# PR5002-S.net
KiCad netlist of a schematic drawn in EAGLE
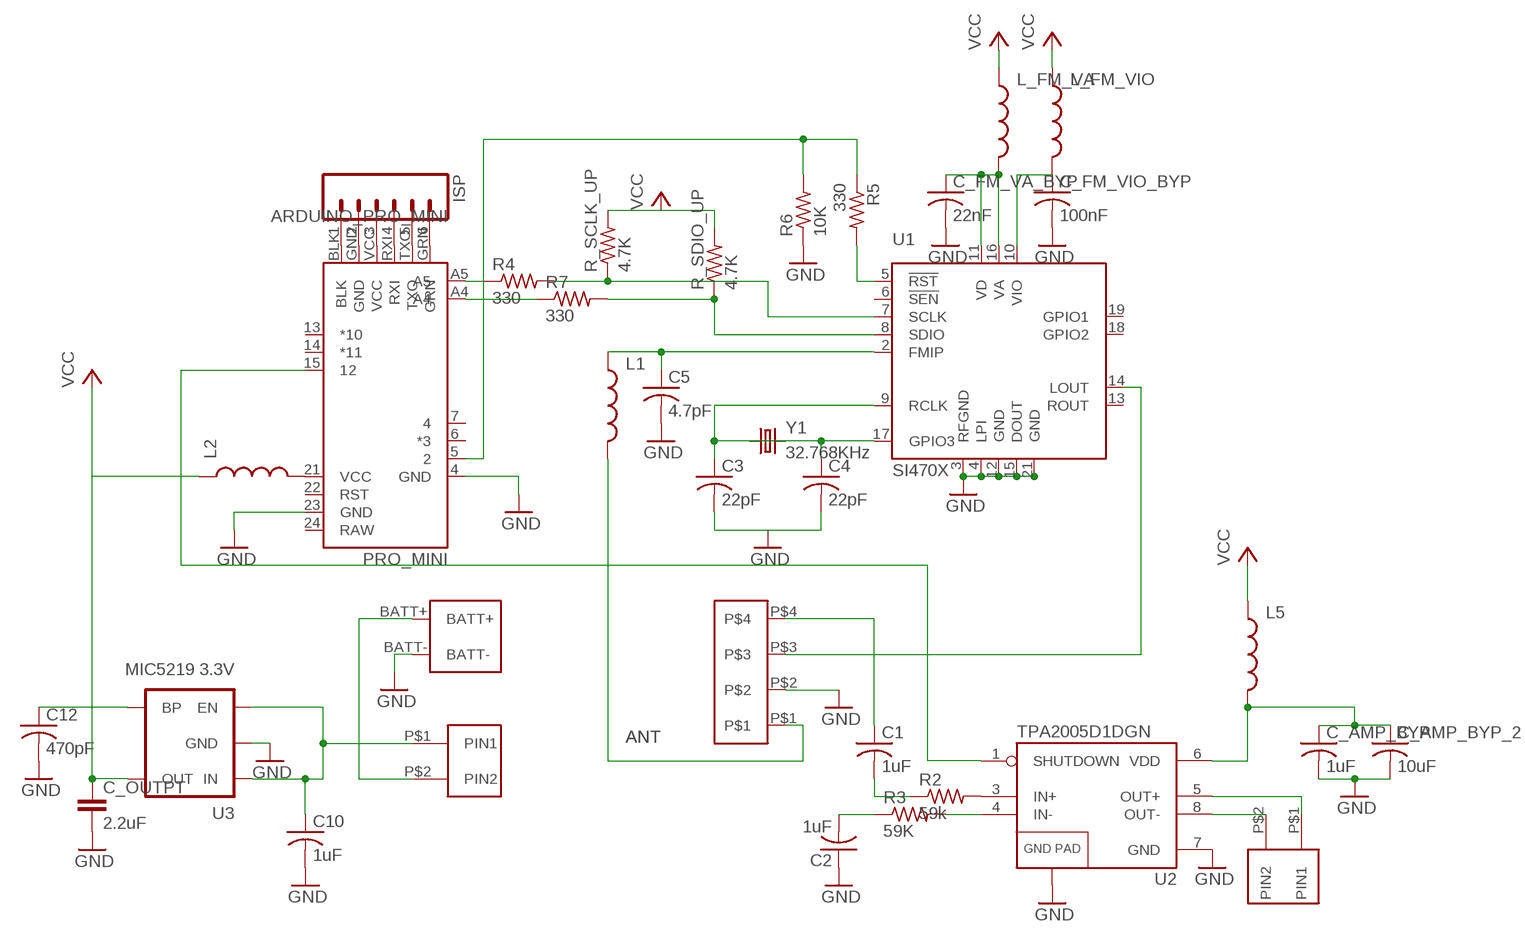
[diagram p0: schematic, sheet 1]

(export (version "E")
  (design (tool "Eeschema 10.0.6"))
  (components
    (comp (ref "ANT/POT_VOL")
      (value "OSTVN04")
      (footprint "eagle-import:OSTVN04")
      (libsource (lib "eagle-import") (part "OSTVN04"))
    )
    (comp (ref "BATT_IN")
      (value "KEYSTONE_2479_3XAAA_BOTTOM")
      (footprint "eagle-import:KEYSTONE_2479_3XAAA_BOTTOM")
      (libsource (lib "eagle-import") (part "KEYSTONE_2479_3XAAA_BOTTOM"))
    )
    (comp (ref "C1")
      (value "1uF")
      (footprint "eagle-import:C0603")
      (libsource (lib "eagle-import") (part "C-USC0603"))
    )
    (comp (ref "C2")
      (value "1uF")
      (footprint "eagle-import:C0603")
      (libsource (lib "eagle-import") (part "C-USC0603"))
    )
    (comp (ref "C3")
      (value "22pF")
      (footprint "eagle-import:C0603")
      (libsource (lib "eagle-import") (part "C-USC0603"))
    )
    (comp (ref "C4")
      (value "22pF")
      (footprint "eagle-import:C0603")
      (libsource (lib "eagle-import") (part "C-USC0603"))
    )
    (comp (ref "C5")
      (value "4.7pF")
      (footprint "eagle-import:C0603")
      (libsource (lib "eagle-import") (part "C-USC0603"))
    )
    (comp (ref "C10")
      (value "1uF")
      (footprint "eagle-import:C0603")
      (libsource (lib "eagle-import") (part "C-USC0603"))
    )
    (comp (ref "C12")
      (value "470pF")
      (footprint "eagle-import:C0603")
      (libsource (lib "eagle-import") (part "C-USC0603"))
    )
    (comp (ref "C_AMP_BYP")
      (value "1uF")
      (footprint "eagle-import:C0603")
      (libsource (lib "eagle-import") (part "C-USC0603"))
    )
    (comp (ref "C_AMP_BYP_2")
      (value "10uF")
      (footprint "eagle-import:C0603")
      (libsource (lib "eagle-import") (part "C-USC0603"))
    )
    (comp (ref "C_FM_VA_BYP")
      (value "22nF")
      (footprint "eagle-import:C0603")
      (libsource (lib "eagle-import") (part "C-USC0603"))
    )
    (comp (ref "C_FM_VIO_BYP")
      (value "100nF")
      (footprint "eagle-import:C0603")
      (libsource (lib "eagle-import") (part "C-USC0603"))
    )
    (comp (ref "C_OUTPT")
      (value "2.2uF")
      (footprint "eagle-import:VISHAY_TR3C")
      (libsource (lib "eagle-import") (part "VISHAY_TR3C"))
    )
    (comp (ref "ISP")
      (value "M06LOCK_LONGPADS")
      (footprint "eagle-import:1X06_LOCK_LONGPADS")
      (libsource (lib "eagle-import") (part "M06LOCK_LONGPADS"))
    )
    (comp (ref "L1")
      (value "INDUCTOR0805")
      (footprint "eagle-import:0805")
      (libsource (lib "eagle-import") (part "INDUCTOR0805"))
    )
    (comp (ref "L2")
      (value "INDUCTOR0603")
      (footprint "eagle-import:0603")
      (libsource (lib "eagle-import") (part "INDUCTOR0603"))
    )
    (comp (ref "L5")
      (value "INDUCTOR0603")
      (footprint "eagle-import:0603")
      (libsource (lib "eagle-import") (part "INDUCTOR0603"))
    )
    (comp (ref "L_FM_VA")
      (value "INDUCTOR0603")
      (footprint "eagle-import:0603")
      (libsource (lib "eagle-import") (part "INDUCTOR0603"))
    )
    (comp (ref "L_FM_VIO")
      (value "INDUCTOR0603")
      (footprint "eagle-import:0603")
      (libsource (lib "eagle-import") (part "INDUCTOR0603"))
    )
    (comp (ref "POT_SW")
      (value "OSTVN02")
      (footprint "eagle-import:OSTVN02")
      (libsource (lib "eagle-import") (part "OSTVN02"))
    )
    (comp (ref "PRO_MINI")
      (value "ARDUINO_PRO_MINI")
      (footprint "eagle-import:ARDUINO_PRO_MINI")
      (libsource (lib "eagle-import") (part "ARDUINO_PRO_MINI"))
    )
    (comp (ref "R2")
      (value "59k")
      (footprint "eagle-import:R0603")
      (libsource (lib "eagle-import") (part "R-US_R0603"))
    )
    (comp (ref "R3")
      (value "59K")
      (footprint "eagle-import:R0603")
      (libsource (lib "eagle-import") (part "R-US_R0603"))
    )
    (comp (ref "R4")
      (value "330")
      (footprint "eagle-import:R0603")
      (libsource (lib "eagle-import") (part "R-US_R0603"))
    )
    (comp (ref "R5")
      (value "330")
      (footprint "eagle-import:R0603")
      (libsource (lib "eagle-import") (part "R-US_R0603"))
    )
    (comp (ref "R6")
      (value "10K")
      (footprint "eagle-import:R0603")
      (libsource (lib "eagle-import") (part "R-US_R0603"))
    )
    (comp (ref "R7")
      (value "330")
      (footprint "eagle-import:R0603")
      (libsource (lib "eagle-import") (part "R-US_R0603"))
    )
    (comp (ref "R_SCLK_UP")
      (value "4.7K")
      (footprint "eagle-import:R0603")
      (libsource (lib "eagle-import") (part "R-US_R0603"))
    )
    (comp (ref "R_SDIO_UP")
      (value "4.7K")
      (footprint "eagle-import:R0603")
      (libsource (lib "eagle-import") (part "R-US_R0603"))
    )
    (comp (ref "SPKR")
      (value "OSTVN02")
      (footprint "eagle-import:OSTVN02")
      (libsource (lib "eagle-import") (part "OSTVN02"))
    )
    (comp (ref "U1")
      (value "SI470X")
      (footprint "eagle-import:SI470X")
      (libsource (lib "eagle-import") (part "SI470X"))
    )
    (comp (ref "U2")
      (value "TPA2005D1DGN")
      (footprint "eagle-import:POWER-SOP8")
      (libsource (lib "eagle-import") (part "TPA2005D1DGN"))
    )
    (comp (ref "U3")
      (value "MIC5219 3.3V")
      (footprint "eagle-import:SOT23-5")
      (libsource (lib "eagle-import") (part "V_REG_MIC52193.3V"))
    )
    (comp (ref "Y1")
      (value "32.768KHz")
      (footprint "eagle-import:CRYSTAL-32KHZ-SMD")
      (libsource (lib "eagle-import") (part "CRYSTAL32-SMD"))
    )
  )
  (nets
    (net (code "1") (name "/ANT") (class "Default")
      (node (ref "ANT/POT_VOL") (pin "P$1") (pinfunction "P$1_P$1") (pintype "bidirectional"))
      (node (ref "L1") (pin "2") (pinfunction "2_2") (pintype "passive"))
    )
    (net (code "2") (name "GND") (class "Default")
      (node (ref "ANT/POT_VOL") (pin "P$2") (pinfunction "P$2_P$2") (pintype "bidirectional"))
      (node (ref "BATT_IN") (pin "BATT-") (pinfunction "BATT-_BATT-") (pintype "bidirectional"))
      (node (ref "C10") (pin "2") (pinfunction "2_2") (pintype "passive"))
      (node (ref "C12") (pin "2") (pinfunction "2_2") (pintype "passive"))
      (node (ref "C2") (pin "1") (pinfunction "1_1") (pintype "passive"))
      (node (ref "C3") (pin "2") (pinfunction "2_2") (pintype "passive"))
      (node (ref "C4") (pin "2") (pinfunction "2_2") (pintype "passive"))
      (node (ref "C5") (pin "2") (pinfunction "2_2") (pintype "passive"))
      (node (ref "C_AMP_BYP") (pin "2") (pinfunction "2_2") (pintype "passive"))
      (node (ref "C_AMP_BYP_2") (pin "2") (pinfunction "2_2") (pintype "passive"))
      (node (ref "C_FM_VA_BYP") (pin "2") (pinfunction "2_2") (pintype "passive"))
      (node (ref "C_FM_VIO_BYP") (pin "2") (pinfunction "2_2") (pintype "passive"))
      (node (ref "C_OUTPT") (pin "P$2") (pinfunction "2_P$2") (pintype "passive"))
      (node (ref "PRO_MINI") (pin "23") (pinfunction "GND_23") (pintype "bidirectional"))
      (node (ref "PRO_MINI") (pin "4") (pinfunction "GND_4") (pintype "bidirectional"))
      (node (ref "R6") (pin "1") (pinfunction "1_1") (pintype "passive"))
      (node (ref "U1") (pin "12") (pinfunction "GND_12") (pintype "bidirectional"))
      (node (ref "U1") (pin "15") (pinfunction "DOUT_15") (pintype "bidirectional"))
      (node (ref "U1") (pin "21") (pinfunction "GND_21") (pintype "bidirectional"))
      (node (ref "U1") (pin "3") (pinfunction "RFGND_3") (pintype "bidirectional"))
      (node (ref "U1") (pin "4") (pinfunction "LPI_4") (pintype "bidirectional"))
      (node (ref "U2") (pin "7") (pinfunction "GND_7") (pintype "power_in"))
      (node (ref "U2") (pin "9") (pinfunction "GND_9") (pintype "power_in"))
      (node (ref "U3") (pin "2") (pinfunction "GND_2") (pintype "input"))
    )
    (net (code "3") (name "Net-(ANT/POT_VOL-PadP$4)") (class "Default")
      (node (ref "ANT/POT_VOL") (pin "P$4") (pinfunction "P$4_P$4") (pintype "bidirectional"))
      (node (ref "C1") (pin "1") (pinfunction "1_1") (pintype "passive"))
    )
    (net (code "4") (name "Net-(C1-Pad2)") (class "Default")
      (node (ref "C1") (pin "2") (pinfunction "2_2") (pintype "passive"))
      (node (ref "R2") (pin "1") (pinfunction "1_1") (pintype "passive"))
    )
    (net (code "5") (name "Net-(C2-Pad2)") (class "Default")
      (node (ref "C2") (pin "2") (pinfunction "2_2") (pintype "passive"))
      (node (ref "R3") (pin "1") (pinfunction "1_1") (pintype "passive"))
    )
    (net (code "6") (name "Net-(ISP-Pad1)") (class "Default")
      (node (ref "ISP") (pin "1") (pinfunction "1_1") (pintype "passive"))
      (node (ref "PRO_MINI") (pin "BLK") (pinfunction "BLK_BLK") (pintype "bidirectional"))
    )
    (net (code "7") (name "Net-(ISP-Pad2)") (class "Default")
      (node (ref "ISP") (pin "2") (pinfunction "2_2") (pintype "passive"))
      (node (ref "PRO_MINI") (pin "GND") (pinfunction "GND_GND") (pintype "bidirectional"))
    )
    (net (code "8") (name "Net-(ISP-Pad3)") (class "Default")
      (node (ref "ISP") (pin "3") (pinfunction "3_3") (pintype "passive"))
      (node (ref "PRO_MINI") (pin "VCC") (pinfunction "VCC_VCC") (pintype "bidirectional"))
    )
    (net (code "9") (name "Net-(ISP-Pad4)") (class "Default")
      (node (ref "ISP") (pin "4") (pinfunction "4_4") (pintype "passive"))
      (node (ref "PRO_MINI") (pin "RXI") (pinfunction "RXI_RXI") (pintype "bidirectional"))
    )
    (net (code "10") (name "Net-(ISP-Pad5)") (class "Default")
      (node (ref "ISP") (pin "5") (pinfunction "5_5") (pintype "passive"))
      (node (ref "PRO_MINI") (pin "TXO") (pinfunction "TXO_TXO") (pintype "bidirectional"))
    )
    (net (code "11") (name "Net-(ISP-Pad6)") (class "Default")
      (node (ref "ISP") (pin "6") (pinfunction "6_6") (pintype "passive"))
      (node (ref "PRO_MINI") (pin "GRN") (pinfunction "GRN_GRN") (pintype "bidirectional"))
    )
    (net (code "12") (name "Net-(L2-Pad2)") (class "Default")
      (node (ref "L2") (pin "2") (pinfunction "2_2") (pintype "passive"))
      (node (ref "PRO_MINI") (pin "21") (pinfunction "VCC_21") (pintype "bidirectional"))
    )
    (net (code "13") (name "Net-(POT_SW-PIN1)") (class "Default")
      (node (ref "C10") (pin "1") (pinfunction "1_1") (pintype "passive"))
      (node (ref "POT_SW") (pin "P$1") (pinfunction "PIN1_P$1") (pintype "bidirectional"))
      (node (ref "U3") (pin "1") (pinfunction "IN_1") (pintype "input"))
      (node (ref "U3") (pin "3") (pinfunction "EN_3") (pintype "input"))
    )
    (net (code "14") (name "Net-(POT_SW-PIN2)") (class "Default")
      (node (ref "BATT_IN") (pin "BATT+") (pinfunction "BATT+_BATT+") (pintype "bidirectional"))
      (node (ref "POT_SW") (pin "P$2") (pinfunction "PIN2_P$2") (pintype "bidirectional"))
    )
    (net (code "15") (name "Net-(PRO_MINI-2)") (class "Default")
      (node (ref "PRO_MINI") (pin "5") (pinfunction "2_5") (pintype "bidirectional"))
      (node (ref "R5") (pin "1") (pinfunction "1_1") (pintype "passive"))
      (node (ref "R6") (pin "2") (pinfunction "2_2") (pintype "passive"))
    )
    (net (code "16") (name "Net-(PRO_MINI-12)") (class "Default")
      (node (ref "PRO_MINI") (pin "15") (pinfunction "12_15") (pintype "bidirectional"))
      (node (ref "U2") (pin "1") (pinfunction "SHUTDOWN_1") (pintype "input"))
    )
    (net (code "17") (name "Net-(PRO_MINI-PadA4)") (class "Default")
      (node (ref "PRO_MINI") (pin "A4") (pinfunction "A4_A4") (pintype "bidirectional"))
      (node (ref "R7") (pin "1") (pinfunction "1_1") (pintype "passive"))
    )
    (net (code "18") (name "Net-(PRO_MINI-PadA5)") (class "Default")
      (node (ref "PRO_MINI") (pin "A5") (pinfunction "A5_A5") (pintype "bidirectional"))
      (node (ref "R4") (pin "1") (pinfunction "1_1") (pintype "passive"))
    )
    (net (code "19") (name "Net-(SPKR-PIN1)") (class "Default")
      (node (ref "SPKR") (pin "P$1") (pinfunction "PIN1_P$1") (pintype "bidirectional"))
      (node (ref "U2") (pin "5") (pinfunction "OUT+_5") (pintype "bidirectional"))
    )
    (net (code "20") (name "Net-(SPKR-PIN2)") (class "Default")
      (node (ref "SPKR") (pin "P$2") (pinfunction "PIN2_P$2") (pintype "bidirectional"))
      (node (ref "U2") (pin "8") (pinfunction "OUT-_8") (pintype "bidirectional"))
    )
    (net (code "21") (name "Net-(U1-FMIP)") (class "Default")
      (node (ref "C5") (pin "1") (pinfunction "1_1") (pintype "passive"))
      (node (ref "L1") (pin "1") (pinfunction "1_1") (pintype "passive"))
      (node (ref "U1") (pin "2") (pinfunction "FMIP_2") (pintype "bidirectional"))
    )
    (net (code "22") (name "Net-(U1-GPIO3)") (class "Default")
      (node (ref "C4") (pin "1") (pinfunction "1_1") (pintype "passive"))
      (node (ref "U1") (pin "17") (pinfunction "GPIO3_17") (pintype "bidirectional"))
      (node (ref "Y1") (pin "X1") (pinfunction "1_X1") (pintype "passive"))
    )
    (net (code "23") (name "Net-(U1-LOUT)") (class "Default")
      (node (ref "ANT/POT_VOL") (pin "P$3") (pinfunction "P$3_P$3") (pintype "bidirectional"))
      (node (ref "U1") (pin "14") (pinfunction "LOUT_14") (pintype "bidirectional"))
    )
    (net (code "24") (name "Net-(U1-RCLK)") (class "Default")
      (node (ref "C3") (pin "1") (pinfunction "1_1") (pintype "passive"))
      (node (ref "U1") (pin "9") (pinfunction "RCLK_9") (pintype "bidirectional"))
      (node (ref "Y1") (pin "X2") (pinfunction "2_X2") (pintype "passive"))
    )
    (net (code "25") (name "Net-(U1-SCLK)") (class "Default")
      (node (ref "R4") (pin "2") (pinfunction "2_2") (pintype "passive"))
      (node (ref "R_SCLK_UP") (pin "1") (pinfunction "1_1") (pintype "passive"))
      (node (ref "U1") (pin "7") (pinfunction "SCLK_7") (pintype "bidirectional"))
    )
    (net (code "26") (name "Net-(U1-SDIO)") (class "Default")
      (node (ref "R7") (pin "2") (pinfunction "2_2") (pintype "passive"))
      (node (ref "R_SDIO_UP") (pin "1") (pinfunction "1_1") (pintype "passive"))
      (node (ref "U1") (pin "8") (pinfunction "SDIO_8") (pintype "bidirectional"))
    )
    (net (code "27") (name "Net-(U1-VA)") (class "Default")
      (node (ref "C_FM_VA_BYP") (pin "1") (pinfunction "1_1") (pintype "passive"))
      (node (ref "L_FM_VA") (pin "2") (pinfunction "2_2") (pintype "passive"))
      (node (ref "U1") (pin "11") (pinfunction "VD_11") (pintype "bidirectional"))
      (node (ref "U1") (pin "16") (pinfunction "VA_16") (pintype "bidirectional"))
    )
    (net (code "28") (name "Net-(U1-VIO)") (class "Default")
      (node (ref "C_FM_VIO_BYP") (pin "1") (pinfunction "1_1") (pintype "passive"))
      (node (ref "L_FM_VIO") (pin "2") (pinfunction "2_2") (pintype "passive"))
      (node (ref "U1") (pin "10") (pinfunction "VIO_10") (pintype "bidirectional"))
    )
    (net (code "29") (name "Net-(U1-~{RST})") (class "Default")
      (node (ref "R5") (pin "2") (pinfunction "2_2") (pintype "passive"))
      (node (ref "U1") (pin "5") (pinfunction "~{RST}_5") (pintype "bidirectional"))
    )
    (net (code "30") (name "Net-(U2-IN+)") (class "Default")
      (node (ref "R2") (pin "2") (pinfunction "2_2") (pintype "passive"))
      (node (ref "U2") (pin "3") (pinfunction "IN+_3") (pintype "bidirectional"))
    )
    (net (code "31") (name "Net-(U2-IN-)") (class "Default")
      (node (ref "R3") (pin "2") (pinfunction "2_2") (pintype "passive"))
      (node (ref "U2") (pin "4") (pinfunction "IN-_4") (pintype "bidirectional"))
    )
    (net (code "32") (name "Net-(U2-VDD)") (class "Default")
      (node (ref "C_AMP_BYP") (pin "1") (pinfunction "1_1") (pintype "passive"))
      (node (ref "C_AMP_BYP_2") (pin "1") (pinfunction "1_1") (pintype "passive"))
      (node (ref "L5") (pin "2") (pinfunction "2_2") (pintype "passive"))
      (node (ref "U2") (pin "6") (pinfunction "VDD_6") (pintype "power_in"))
    )
    (net (code "33") (name "Net-(U3-BP)") (class "Default")
      (node (ref "C12") (pin "1") (pinfunction "1_1") (pintype "passive"))
      (node (ref "U3") (pin "4") (pinfunction "BP_4") (pintype "input"))
    )
    (net (code "34") (name "VCC") (class "Default")
      (node (ref "C_OUTPT") (pin "P$1") (pinfunction "1_P$1") (pintype "passive"))
      (node (ref "L2") (pin "1") (pinfunction "1_1") (pintype "passive"))
      (node (ref "L5") (pin "1") (pinfunction "1_1") (pintype "passive"))
      (node (ref "L_FM_VA") (pin "1") (pinfunction "1_1") (pintype "passive"))
      (node (ref "L_FM_VIO") (pin "1") (pinfunction "1_1") (pintype "passive"))
      (node (ref "R_SCLK_UP") (pin "2") (pinfunction "2_2") (pintype "passive"))
      (node (ref "R_SDIO_UP") (pin "2") (pinfunction "2_2") (pintype "passive"))
      (node (ref "U3") (pin "5") (pinfunction "OUT_5") (pintype "passive"))
    )
    (net (code "35") (name "unconnected-(PRO_MINI-*3-Pad6)") (class "Default")
      (node (ref "PRO_MINI") (pin "6") (pinfunction "*3_6") (pintype "bidirectional"))
    )
    (net (code "36") (name "unconnected-(PRO_MINI-*10-Pad13)") (class "Default")
      (node (ref "PRO_MINI") (pin "13") (pinfunction "*10_13") (pintype "bidirectional"))
    )
    (net (code "37") (name "unconnected-(PRO_MINI-*11-Pad14)") (class "Default")
      (node (ref "PRO_MINI") (pin "14") (pinfunction "*11_14") (pintype "bidirectional"))
    )
    (net (code "38") (name "unconnected-(PRO_MINI-4-Pad7)") (class "Default")
      (node (ref "PRO_MINI") (pin "7") (pinfunction "4_7") (pintype "bidirectional"))
    )
    (net (code "39") (name "unconnected-(PRO_MINI-RAW-Pad24)") (class "Default")
      (node (ref "PRO_MINI") (pin "24") (pinfunction "RAW_24") (pintype "bidirectional"))
    )
    (net (code "40") (name "unconnected-(PRO_MINI-RST-Pad22)") (class "Default")
      (node (ref "PRO_MINI") (pin "22") (pinfunction "RST_22") (pintype "bidirectional"))
    )
    (net (code "41") (name "unconnected-(U1-GPIO1-Pad19)") (class "Default")
      (node (ref "U1") (pin "19") (pinfunction "GPIO1_19") (pintype "bidirectional"))
    )
    (net (code "42") (name "unconnected-(U1-GPIO2-Pad18)") (class "Default")
      (node (ref "U1") (pin "18") (pinfunction "GPIO2_18") (pintype "bidirectional"))
    )
    (net (code "43") (name "unconnected-(U1-ROUT-Pad13)") (class "Default")
      (node (ref "U1") (pin "13") (pinfunction "ROUT_13") (pintype "bidirectional"))
    )
    (net (code "44") (name "unconnected-(U1-~{SEN}-Pad6)") (class "Default")
      (node (ref "U1") (pin "6") (pinfunction "~{SEN}_6") (pintype "bidirectional"))
    )
  )
)
